# Sheet_1_2026-03-24.net
KiCad netlist of a schematic drawn in Altium Designer
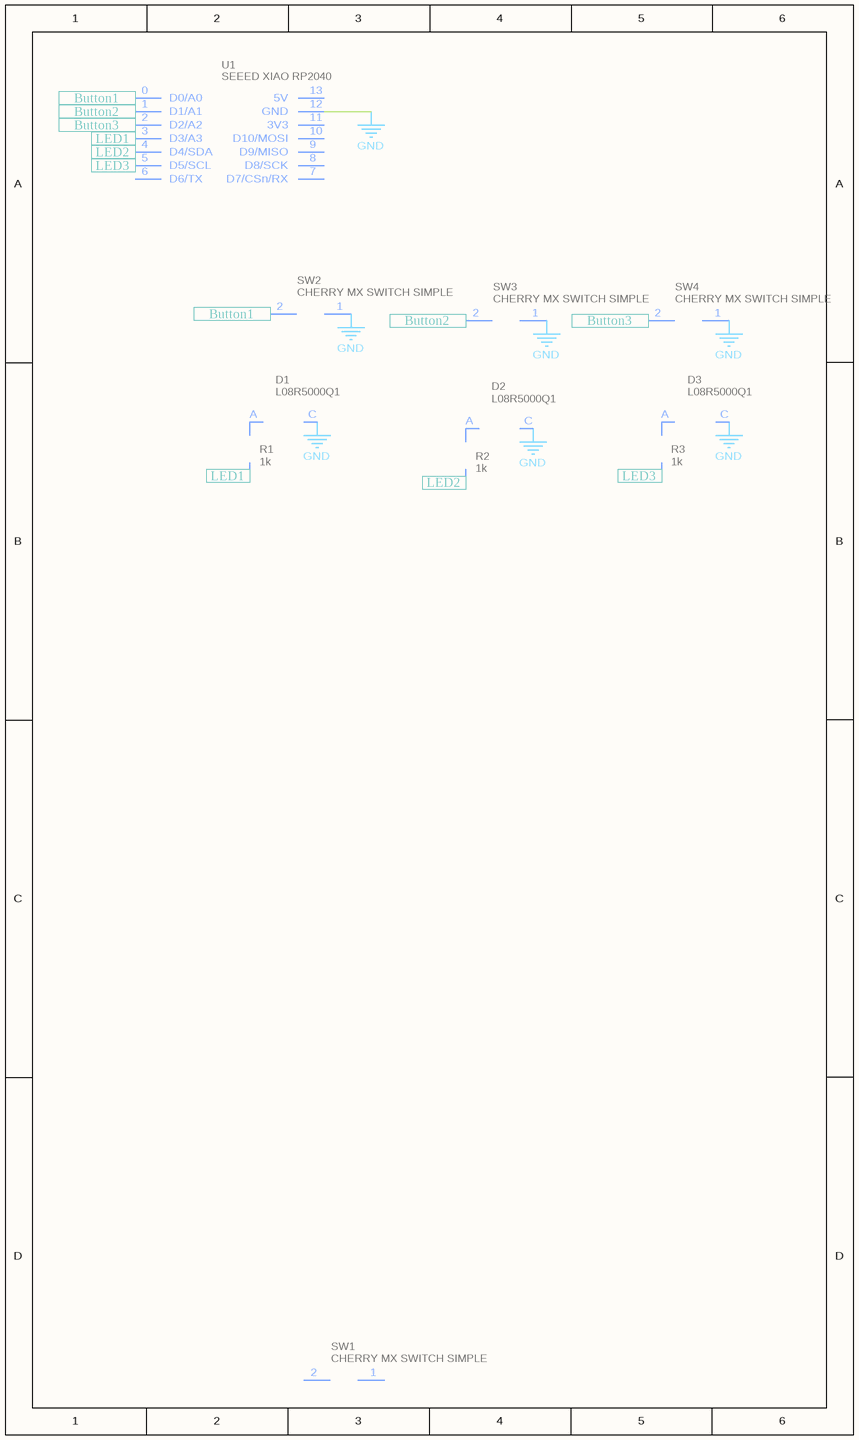
[diagram p0: Sheet_1_2026-03-24.schdoc]

(export (version "E")
  (design (tool "Eeschema 10.0.6"))
  (components
    (comp (ref "D1")
      (value "L08R5000Q1")
      (fields (field (name "CONTRIBUTOR") "aleca"))
      (libsource (lib "altium-import") (part "root_0_L08R5000Q1_"))
    )
    (comp (ref "D2")
      (value "L08R5000Q1")
      (fields (field (name "CONTRIBUTOR") "aleca"))
      (libsource (lib "altium-import") (part "root_0_L08R5000Q1_"))
    )
    (comp (ref "D3")
      (value "L08R5000Q1")
      (fields (field (name "CONTRIBUTOR") "aleca"))
      (libsource (lib "altium-import") (part "root_0_L08R5000Q1_"))
    )
    (comp (ref "R1")
      (value "1k")
      (fields (field (name "CONTRIBUTOR") "LCEDA_Lib"))
      (libsource (lib "altium-import") (part "root_1_1k_"))
    )
    (comp (ref "R2")
      (value "1k")
      (fields (field (name "CONTRIBUTOR") "LCEDA_Lib"))
      (libsource (lib "altium-import") (part "root_1_1k_"))
    )
    (comp (ref "R3")
      (value "1k")
      (fields (field (name "CONTRIBUTOR") "LCEDA_Lib"))
      (libsource (lib "altium-import") (part "root_1_1k_"))
    )
    (comp (ref "SW1")
      (value "CHERRY MX SWITCH SIMPLE")
      (fields (field (name "CONTRIBUTOR") "geocipher"))
      (libsource (lib "altium-import") (part "root_0_CHERRY MX SWITCH SIMPLE_"))
    )
    (comp (ref "SW2")
      (value "CHERRY MX SWITCH SIMPLE")
      (fields (field (name "CONTRIBUTOR") "geocipher"))
      (libsource (lib "altium-import") (part "root_0_CHERRY MX SWITCH SIMPLE_"))
    )
    (comp (ref "SW3")
      (value "CHERRY MX SWITCH SIMPLE")
      (fields (field (name "CONTRIBUTOR") "geocipher"))
      (libsource (lib "altium-import") (part "root_0_CHERRY MX SWITCH SIMPLE_"))
    )
    (comp (ref "SW4")
      (value "CHERRY MX SWITCH SIMPLE")
      (fields (field (name "CONTRIBUTOR") "geocipher"))
      (libsource (lib "altium-import") (part "root_0_CHERRY MX SWITCH SIMPLE_"))
    )
    (comp (ref "U1")
      (value "SEEED XIAO RP2040")
      (fields (field (name "CONTRIBUTOR") "Jostein Løwer"))
      (libsource (lib "altium-import") (part "root_0_SEEED XIAO RP2040_"))
    )
  )
  (nets
    (net (code "1") (name "/Button1") (class "Default")
      (node (ref "SW2") (pin "2") (pinfunction "2_2") (pintype "passive"))
      (node (ref "U1") (pin "0") (pinfunction "D0/A0_0") (pintype "passive"))
    )
    (net (code "2") (name "/Button2") (class "Default")
      (node (ref "SW3") (pin "2") (pinfunction "2_2") (pintype "passive"))
      (node (ref "U1") (pin "1") (pinfunction "D1/A1_1") (pintype "passive"))
    )
    (net (code "3") (name "/Button3") (class "Default")
      (node (ref "SW4") (pin "2") (pinfunction "2_2") (pintype "passive"))
      (node (ref "U1") (pin "2") (pinfunction "D2/A2_2") (pintype "passive"))
    )
    (net (code "4") (name "/LED1") (class "Default")
      (node (ref "R1") (pin "1") (pinfunction "1_1") (pintype "passive"))
      (node (ref "U1") (pin "3") (pinfunction "D3/A3_3") (pintype "passive"))
    )
    (net (code "5") (name "/LED2") (class "Default")
      (node (ref "R2") (pin "1") (pinfunction "1_1") (pintype "passive"))
      (node (ref "U1") (pin "4") (pinfunction "D4/SDA_4") (pintype "passive"))
    )
    (net (code "6") (name "/LED3") (class "Default")
      (node (ref "R3") (pin "1") (pinfunction "1_1") (pintype "passive"))
      (node (ref "U1") (pin "5") (pinfunction "D5/SCL_5") (pintype "passive"))
    )
    (net (code "7") (name "GND") (class "Default")
      (node (ref "D1") (pin "C") (pinfunction "C_C") (pintype "passive"))
      (node (ref "D2") (pin "C") (pinfunction "C_C") (pintype "passive"))
      (node (ref "D3") (pin "C") (pinfunction "C_C") (pintype "passive"))
      (node (ref "SW2") (pin "1") (pinfunction "1_1") (pintype "passive"))
      (node (ref "SW3") (pin "1") (pinfunction "1_1") (pintype "passive"))
      (node (ref "SW4") (pin "1") (pinfunction "1_1") (pintype "passive"))
      (node (ref "U1") (pin "12") (pinfunction "GND_12") (pintype "passive"))
    )
    (net (code "8") (name "Net-(D1-PadA)") (class "Default")
      (node (ref "D1") (pin "A") (pinfunction "A_A") (pintype "passive"))
      (node (ref "R1") (pin "2") (pinfunction "2_2") (pintype "passive"))
    )
    (net (code "9") (name "Net-(D2-PadA)") (class "Default")
      (node (ref "D2") (pin "A") (pinfunction "A_A") (pintype "passive"))
      (node (ref "R2") (pin "2") (pinfunction "2_2") (pintype "passive"))
    )
    (net (code "10") (name "Net-(D3-PadA)") (class "Default")
      (node (ref "D3") (pin "A") (pinfunction "A_A") (pintype "passive"))
      (node (ref "R3") (pin "2") (pinfunction "2_2") (pintype "passive"))
    )
    (net (code "11") (name "unconnected-(SW1-Pad1)") (class "Default")
      (node (ref "SW1") (pin "1") (pinfunction "1_1") (pintype "passive"))
    )
    (net (code "12") (name "unconnected-(SW1-Pad2)") (class "Default")
      (node (ref "SW1") (pin "2") (pinfunction "2_2") (pintype "passive"))
    )
    (net (code "13") (name "unconnected-(U1-3V3-Pad11)") (class "Default")
      (node (ref "U1") (pin "11") (pinfunction "3V3_11") (pintype "passive"))
    )
    (net (code "14") (name "unconnected-(U1-5V-Pad13)") (class "Default")
      (node (ref "U1") (pin "13") (pinfunction "5V_13") (pintype "passive"))
    )
    (net (code "15") (name "unconnected-(U1-D6{slash}TX-Pad6)") (class "Default")
      (node (ref "U1") (pin "6") (pinfunction "D6/TX_6") (pintype "passive"))
    )
    (net (code "16") (name "unconnected-(U1-D7{slash}CSn{slash}RX-Pad7)") (class "Default")
      (node (ref "U1") (pin "7") (pinfunction "D7/CSn/RX_7") (pintype "passive"))
    )
    (net (code "17") (name "unconnected-(U1-D8{slash}SCK-Pad8)") (class "Default")
      (node (ref "U1") (pin "8") (pinfunction "D8/SCK_8") (pintype "passive"))
    )
    (net (code "18") (name "unconnected-(U1-D9{slash}MISO-Pad9)") (class "Default")
      (node (ref "U1") (pin "9") (pinfunction "D9/MISO_9") (pintype "passive"))
    )
    (net (code "19") (name "unconnected-(U1-D10{slash}MOSI-Pad10)") (class "Default")
      (node (ref "U1") (pin "10") (pinfunction "D10/MOSI_10") (pintype "passive"))
    )
  )
)
